# PAMonitorAP2.net
KiCad netlist of a schematic drawn in EAGLE
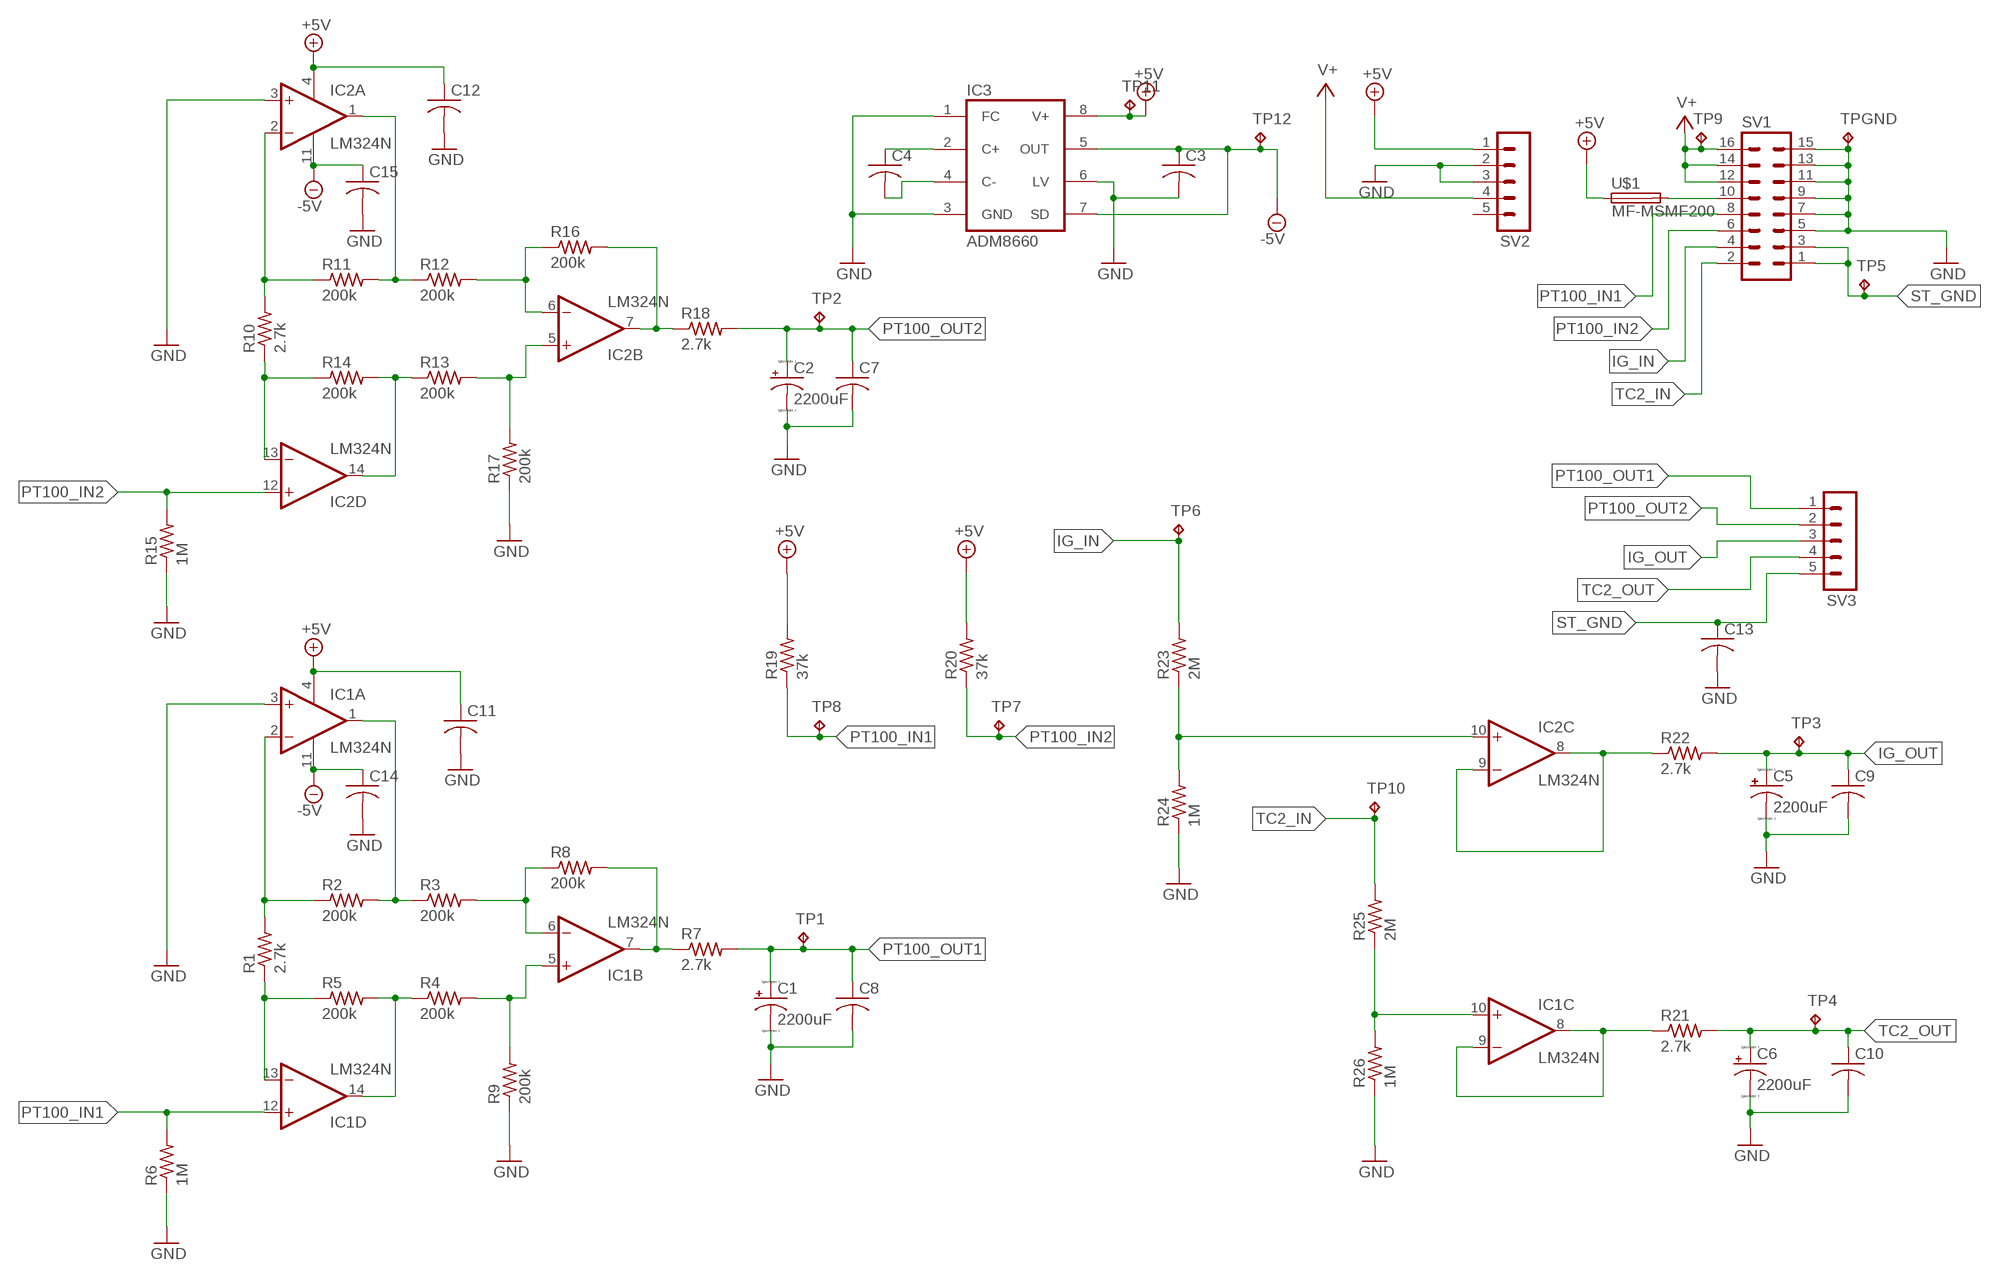
[diagram p0: schematic, sheet 1]

(export (version "E")
  (design (tool "Eeschema 10.0.6"))
  (components
    (comp (ref "C1")
      (value "2200uF")
      (footprint "eagle-import:E5-10,5")
      (libsource (lib "eagle-import") (part "CPOL-USE5-10.5"))
    )
    (comp (ref "C2")
      (value "2200uF")
      (footprint "eagle-import:E5-10,5")
      (libsource (lib "eagle-import") (part "CPOL-USE5-10.5"))
    )
    (comp (ref "C3")
      (value "C-US025-025X050")
      (footprint "eagle-import:C025-025X050")
      (libsource (lib "eagle-import") (part "C-US025-025X050"))
    )
    (comp (ref "C4")
      (value "C-US025-025X050")
      (footprint "eagle-import:C025-025X050")
      (libsource (lib "eagle-import") (part "C-US025-025X050"))
    )
    (comp (ref "C5")
      (value "2200uF")
      (footprint "eagle-import:E5-10,5")
      (libsource (lib "eagle-import") (part "CPOL-USE5-10.5"))
    )
    (comp (ref "C6")
      (value "2200uF")
      (footprint "eagle-import:E5-10,5")
      (libsource (lib "eagle-import") (part "CPOL-USE5-10.5"))
    )
    (comp (ref "C7")
      (value "C-US025-025X050")
      (footprint "eagle-import:C025-025X050")
      (libsource (lib "eagle-import") (part "C-US025-025X050"))
    )
    (comp (ref "C8")
      (value "C-US025-025X050")
      (footprint "eagle-import:C025-025X050")
      (libsource (lib "eagle-import") (part "C-US025-025X050"))
    )
    (comp (ref "C9")
      (value "C-US025-025X050")
      (footprint "eagle-import:C025-025X050")
      (libsource (lib "eagle-import") (part "C-US025-025X050"))
    )
    (comp (ref "C10")
      (value "C-US025-025X050")
      (footprint "eagle-import:C025-025X050")
      (libsource (lib "eagle-import") (part "C-US025-025X050"))
    )
    (comp (ref "C11")
      (value "C-US025-025X050")
      (footprint "eagle-import:C025-025X050")
      (libsource (lib "eagle-import") (part "C-US025-025X050"))
    )
    (comp (ref "C12")
      (value "C-US025-025X050")
      (footprint "eagle-import:C025-025X050")
      (libsource (lib "eagle-import") (part "C-US025-025X050"))
    )
    (comp (ref "C13")
      (value "C-US025-025X050")
      (footprint "eagle-import:C025-025X050")
      (libsource (lib "eagle-import") (part "C-US025-025X050"))
    )
    (comp (ref "C14")
      (value "C-US025-025X050")
      (footprint "eagle-import:C025-025X050")
      (libsource (lib "eagle-import") (part "C-US025-025X050"))
    )
    (comp (ref "C15")
      (value "C-US025-025X050")
      (footprint "eagle-import:C025-025X050")
      (libsource (lib "eagle-import") (part "C-US025-025X050"))
    )
    (comp (ref "IC1")
      (value "LM324N")
      (footprint "eagle-import:DIL14")
      (libsource (lib "eagle-import") (part "LM324N"))
    )
    (comp (ref "IC2")
      (value "LM324N")
      (footprint "eagle-import:DIL14")
      (libsource (lib "eagle-import") (part "LM324N"))
    )
    (comp (ref "IC3")
      (value "ADM8660")
      (footprint "eagle-import:ADM8660-DIL08")
      (fields (field (name "MF") "Analog Devices"))
      (libsource (lib "eagle-import") (part "ADM8660"))
    )
    (comp (ref "R1")
      (value "2.7k")
      (footprint "eagle-import:0309_12")
      (libsource (lib "eagle-import") (part "R-US_0309/12"))
    )
    (comp (ref "R2")
      (value "200k")
      (footprint "eagle-import:0309_12")
      (libsource (lib "eagle-import") (part "R-US_0309/12"))
    )
    (comp (ref "R3")
      (value "200k")
      (footprint "eagle-import:0309_12")
      (libsource (lib "eagle-import") (part "R-US_0309/12"))
    )
    (comp (ref "R4")
      (value "200k")
      (footprint "eagle-import:0309_12")
      (libsource (lib "eagle-import") (part "R-US_0309/12"))
    )
    (comp (ref "R5")
      (value "200k")
      (footprint "eagle-import:0309_12")
      (libsource (lib "eagle-import") (part "R-US_0309/12"))
    )
    (comp (ref "R6")
      (value "1M")
      (footprint "eagle-import:0309_12")
      (libsource (lib "eagle-import") (part "R-US_0309/12"))
    )
    (comp (ref "R7")
      (value "2.7k")
      (footprint "eagle-import:0309_12")
      (libsource (lib "eagle-import") (part "R-US_0309/12"))
    )
    (comp (ref "R8")
      (value "200k")
      (footprint "eagle-import:0309_12")
      (libsource (lib "eagle-import") (part "R-US_0309/12"))
    )
    (comp (ref "R9")
      (value "200k")
      (footprint "eagle-import:0309_12")
      (libsource (lib "eagle-import") (part "R-US_0309/12"))
    )
    (comp (ref "R10")
      (value "2.7k")
      (footprint "eagle-import:0309_12")
      (libsource (lib "eagle-import") (part "R-US_0309/12"))
    )
    (comp (ref "R11")
      (value "200k")
      (footprint "eagle-import:0309_12")
      (libsource (lib "eagle-import") (part "R-US_0309/12"))
    )
    (comp (ref "R12")
      (value "200k")
      (footprint "eagle-import:0309_12")
      (libsource (lib "eagle-import") (part "R-US_0309/12"))
    )
    (comp (ref "R13")
      (value "200k")
      (footprint "eagle-import:0309_12")
      (libsource (lib "eagle-import") (part "R-US_0309/12"))
    )
    (comp (ref "R14")
      (value "200k")
      (footprint "eagle-import:0309_12")
      (libsource (lib "eagle-import") (part "R-US_0309/12"))
    )
    (comp (ref "R15")
      (value "1M")
      (footprint "eagle-import:0309_12")
      (libsource (lib "eagle-import") (part "R-US_0309/12"))
    )
    (comp (ref "R16")
      (value "200k")
      (footprint "eagle-import:0309_12")
      (libsource (lib "eagle-import") (part "R-US_0309/12"))
    )
    (comp (ref "R17")
      (value "200k")
      (footprint "eagle-import:0309_12")
      (libsource (lib "eagle-import") (part "R-US_0309/12"))
    )
    (comp (ref "R18")
      (value "2.7k")
      (footprint "eagle-import:0309_12")
      (libsource (lib "eagle-import") (part "R-US_0309/12"))
    )
    (comp (ref "R19")
      (value "37k")
      (footprint "eagle-import:0309_12")
      (libsource (lib "eagle-import") (part "R-US_0309/12"))
    )
    (comp (ref "R20")
      (value "37k")
      (footprint "eagle-import:0309_12")
      (libsource (lib "eagle-import") (part "R-US_0309/12"))
    )
    (comp (ref "R21")
      (value "2.7k")
      (footprint "eagle-import:0309_12")
      (libsource (lib "eagle-import") (part "R-US_0309/12"))
    )
    (comp (ref "R22")
      (value "2.7k")
      (footprint "eagle-import:0309_12")
      (libsource (lib "eagle-import") (part "R-US_0309/12"))
    )
    (comp (ref "R23")
      (value "2M")
      (footprint "eagle-import:0309_12")
      (libsource (lib "eagle-import") (part "R-US_0309/12"))
    )
    (comp (ref "R24")
      (value "1M")
      (footprint "eagle-import:0309_12")
      (libsource (lib "eagle-import") (part "R-US_0309/12"))
    )
    (comp (ref "R25")
      (value "2M")
      (footprint "eagle-import:0309_12")
      (libsource (lib "eagle-import") (part "R-US_0309/12"))
    )
    (comp (ref "R26")
      (value "1M")
      (footprint "eagle-import:0309_12")
      (libsource (lib "eagle-import") (part "R-US_0309/12"))
    )
    (comp (ref "SV1")
      (value "MA08-2")
      (footprint "eagle-import:MA08-2")
      (libsource (lib "eagle-import") (part "MA08-2"))
    )
    (comp (ref "SV2")
      (value "MA05-1")
      (footprint "eagle-import:MA05-1")
      (libsource (lib "eagle-import") (part "MA05-1"))
    )
    (comp (ref "SV3")
      (value "MA05-1")
      (footprint "eagle-import:MA05-1")
      (libsource (lib "eagle-import") (part "MA05-1"))
    )
    (comp (ref "TP1")
      (value "TPB2,54")
      (footprint "eagle-import:B2,54")
      (libsource (lib "eagle-import") (part "TPB2,54"))
    )
    (comp (ref "TP2")
      (value "TPB2,54")
      (footprint "eagle-import:B2,54")
      (libsource (lib "eagle-import") (part "TPB2,54"))
    )
    (comp (ref "TP3")
      (value "TPB2,54")
      (footprint "eagle-import:B2,54")
      (libsource (lib "eagle-import") (part "TPB2,54"))
    )
    (comp (ref "TP4")
      (value "TPB2,54")
      (footprint "eagle-import:B2,54")
      (libsource (lib "eagle-import") (part "TPB2,54"))
    )
    (comp (ref "TP5")
      (value "TPB2,54")
      (footprint "eagle-import:B2,54")
      (libsource (lib "eagle-import") (part "TPB2,54"))
    )
    (comp (ref "TP6")
      (value "TPB2,54")
      (footprint "eagle-import:B2,54")
      (libsource (lib "eagle-import") (part "TPB2,54"))
    )
    (comp (ref "TP7")
      (value "TPB2,54")
      (footprint "eagle-import:B2,54")
      (libsource (lib "eagle-import") (part "TPB2,54"))
    )
    (comp (ref "TP8")
      (value "TPB2,54")
      (footprint "eagle-import:B2,54")
      (libsource (lib "eagle-import") (part "TPB2,54"))
    )
    (comp (ref "TP9")
      (value "TPB2,54")
      (footprint "eagle-import:B2,54")
      (libsource (lib "eagle-import") (part "TPB2,54"))
    )
    (comp (ref "TP10")
      (value "TPB2,54")
      (footprint "eagle-import:B2,54")
      (libsource (lib "eagle-import") (part "TPB2,54"))
    )
    (comp (ref "TP11")
      (value "TPB2,54")
      (footprint "eagle-import:B2,54")
      (libsource (lib "eagle-import") (part "TPB2,54"))
    )
    (comp (ref "TP12")
      (value "TPB2,54")
      (footprint "eagle-import:B2,54")
      (libsource (lib "eagle-import") (part "TPB2,54"))
    )
    (comp (ref "TPGND")
      (value "TPB2,54")
      (footprint "eagle-import:B2,54")
      (libsource (lib "eagle-import") (part "TPB2,54"))
    )
    (comp (ref "U$1")
      (value "MF-MSMF200")
      (footprint "eagle-import:MF-MSMF200")
      (libsource (lib "eagle-import") (part "MF-MSMF050"))
    )
  )
  (nets
    (net (code "1") (name "+5V") (class "Default")
      (node (ref "C11") (pin "1") (pinfunction "1_1") (pintype "passive"))
      (node (ref "C12") (pin "1") (pinfunction "1_1") (pintype "passive"))
      (node (ref "IC1") (pin "4") (pinfunction "V+_4") (pintype "power_in"))
      (node (ref "IC2") (pin "4") (pinfunction "V+_4") (pintype "power_in"))
      (node (ref "IC3") (pin "8") (pinfunction "V+_8") (pintype "power_in"))
      (node (ref "R19") (pin "2") (pinfunction "2_2") (pintype "passive"))
      (node (ref "R20") (pin "2") (pinfunction "2_2") (pintype "passive"))
      (node (ref "SV2") (pin "1") (pinfunction "1_1") (pintype "passive"))
      (node (ref "TP11") (pin "TP") (pinfunction "TP_TP") (pintype "input"))
      (node (ref "U$1") (pin "1") (pinfunction "1_1") (pintype "passive"))
    )
    (net (code "2") (name "-5V") (class "Default")
      (node (ref "C14") (pin "1") (pinfunction "1_1") (pintype "passive"))
      (node (ref "C15") (pin "1") (pinfunction "1_1") (pintype "passive"))
      (node (ref "C3") (pin "1") (pinfunction "1_1") (pintype "passive"))
      (node (ref "IC1") (pin "11") (pinfunction "V-_11") (pintype "power_in"))
      (node (ref "IC2") (pin "11") (pinfunction "V-_11") (pintype "power_in"))
      (node (ref "IC3") (pin "5") (pinfunction "OUT_5") (pintype "power_in"))
      (node (ref "IC3") (pin "7") (pinfunction "SD_7") (pintype "output"))
      (node (ref "TP12") (pin "TP") (pinfunction "TP_TP") (pintype "input"))
    )
    (net (code "3") (name "GND") (class "Default")
      (node (ref "C1") (pin "-") (pinfunction "-_-") (pintype "passive"))
      (node (ref "C10") (pin "2") (pinfunction "2_2") (pintype "passive"))
      (node (ref "C11") (pin "2") (pinfunction "2_2") (pintype "passive"))
      (node (ref "C12") (pin "2") (pinfunction "2_2") (pintype "passive"))
      (node (ref "C13") (pin "2") (pinfunction "2_2") (pintype "passive"))
      (node (ref "C14") (pin "2") (pinfunction "2_2") (pintype "passive"))
      (node (ref "C15") (pin "2") (pinfunction "2_2") (pintype "passive"))
      (node (ref "C2") (pin "-") (pinfunction "-_-") (pintype "passive"))
      (node (ref "C3") (pin "2") (pinfunction "2_2") (pintype "passive"))
      (node (ref "C5") (pin "-") (pinfunction "-_-") (pintype "passive"))
      (node (ref "C6") (pin "-") (pinfunction "-_-") (pintype "passive"))
      (node (ref "C7") (pin "2") (pinfunction "2_2") (pintype "passive"))
      (node (ref "C8") (pin "2") (pinfunction "2_2") (pintype "passive"))
      (node (ref "C9") (pin "2") (pinfunction "2_2") (pintype "passive"))
      (node (ref "IC1") (pin "3") (pinfunction "+IN_3") (pintype "input"))
      (node (ref "IC2") (pin "3") (pinfunction "+IN_3") (pintype "input"))
      (node (ref "IC3") (pin "1") (pinfunction "FC_1") (pintype "input"))
      (node (ref "IC3") (pin "3") (pinfunction "GND_3") (pintype "power_in"))
      (node (ref "IC3") (pin "6") (pinfunction "LV_6") (pintype "passive"))
      (node (ref "R15") (pin "1") (pinfunction "1_1") (pintype "passive"))
      (node (ref "R17") (pin "1") (pinfunction "1_1") (pintype "passive"))
      (node (ref "R24") (pin "1") (pinfunction "1_1") (pintype "passive"))
      (node (ref "R26") (pin "1") (pinfunction "1_1") (pintype "passive"))
      (node (ref "R6") (pin "1") (pinfunction "1_1") (pintype "passive"))
      (node (ref "R9") (pin "1") (pinfunction "1_1") (pintype "passive"))
      (node (ref "SV1") (pin "11") (pinfunction "11_11") (pintype "passive"))
      (node (ref "SV1") (pin "13") (pinfunction "13_13") (pintype "passive"))
      (node (ref "SV1") (pin "15") (pinfunction "15_15") (pintype "passive"))
      (node (ref "SV1") (pin "5") (pinfunction "5_5") (pintype "passive"))
      (node (ref "SV1") (pin "7") (pinfunction "7_7") (pintype "passive"))
      (node (ref "SV1") (pin "9") (pinfunction "9_9") (pintype "passive"))
      (node (ref "SV2") (pin "2") (pinfunction "2_2") (pintype "passive"))
      (node (ref "SV2") (pin "3") (pinfunction "3_3") (pintype "passive"))
      (node (ref "TPGND") (pin "TP") (pinfunction "TP_TP") (pintype "input"))
    )
    (net (code "4") (name "IG_IN") (class "Default")
      (node (ref "R23") (pin "2") (pinfunction "2_2") (pintype "passive"))
      (node (ref "SV1") (pin "4") (pinfunction "4_4") (pintype "passive"))
      (node (ref "TP6") (pin "TP") (pinfunction "TP_TP") (pintype "input"))
    )
    (net (code "5") (name "IG_OUT") (class "Default")
      (node (ref "C5") (pin "+") (pinfunction "+_+") (pintype "passive"))
      (node (ref "C9") (pin "1") (pinfunction "1_1") (pintype "passive"))
      (node (ref "R22") (pin "2") (pinfunction "2_2") (pintype "passive"))
      (node (ref "SV3") (pin "3") (pinfunction "3_3") (pintype "passive"))
      (node (ref "TP3") (pin "TP") (pinfunction "TP_TP") (pintype "input"))
    )
    (net (code "6") (name "Net-(IC1A--IN)") (class "Default")
      (node (ref "IC1") (pin "2") (pinfunction "-IN_2") (pintype "input"))
      (node (ref "R1") (pin "2") (pinfunction "2_2") (pintype "passive"))
      (node (ref "R2") (pin "1") (pinfunction "1_1") (pintype "passive"))
    )
    (net (code "7") (name "Net-(IC1A-OUT)") (class "Default")
      (node (ref "IC1") (pin "1") (pinfunction "OUT_1") (pintype "output"))
      (node (ref "R2") (pin "2") (pinfunction "2_2") (pintype "passive"))
      (node (ref "R3") (pin "1") (pinfunction "1_1") (pintype "passive"))
    )
    (net (code "8") (name "Net-(IC1B-+IN)") (class "Default")
      (node (ref "IC1") (pin "5") (pinfunction "+IN_5") (pintype "input"))
      (node (ref "R4") (pin "2") (pinfunction "2_2") (pintype "passive"))
      (node (ref "R9") (pin "2") (pinfunction "2_2") (pintype "passive"))
    )
    (net (code "9") (name "Net-(IC1B--IN)") (class "Default")
      (node (ref "IC1") (pin "6") (pinfunction "-IN_6") (pintype "input"))
      (node (ref "R3") (pin "2") (pinfunction "2_2") (pintype "passive"))
      (node (ref "R8") (pin "1") (pinfunction "1_1") (pintype "passive"))
    )
    (net (code "10") (name "Net-(IC1B-OUT)") (class "Default")
      (node (ref "IC1") (pin "7") (pinfunction "OUT_7") (pintype "output"))
      (node (ref "R7") (pin "1") (pinfunction "1_1") (pintype "passive"))
      (node (ref "R8") (pin "2") (pinfunction "2_2") (pintype "passive"))
    )
    (net (code "11") (name "Net-(IC1C-+IN)") (class "Default")
      (node (ref "IC1") (pin "10") (pinfunction "+IN_10") (pintype "input"))
      (node (ref "R25") (pin "1") (pinfunction "1_1") (pintype "passive"))
      (node (ref "R26") (pin "2") (pinfunction "2_2") (pintype "passive"))
    )
    (net (code "12") (name "Net-(IC1C--IN)") (class "Default")
      (node (ref "IC1") (pin "8") (pinfunction "OUT_8") (pintype "output"))
      (node (ref "IC1") (pin "9") (pinfunction "-IN_9") (pintype "input"))
      (node (ref "R21") (pin "1") (pinfunction "1_1") (pintype "passive"))
    )
    (net (code "13") (name "Net-(IC1D--IN)") (class "Default")
      (node (ref "IC1") (pin "13") (pinfunction "-IN_13") (pintype "input"))
      (node (ref "R1") (pin "1") (pinfunction "1_1") (pintype "passive"))
      (node (ref "R5") (pin "1") (pinfunction "1_1") (pintype "passive"))
    )
    (net (code "14") (name "Net-(IC1D-OUT)") (class "Default")
      (node (ref "IC1") (pin "14") (pinfunction "OUT_14") (pintype "output"))
      (node (ref "R4") (pin "1") (pinfunction "1_1") (pintype "passive"))
      (node (ref "R5") (pin "2") (pinfunction "2_2") (pintype "passive"))
    )
    (net (code "15") (name "Net-(IC2A--IN)") (class "Default")
      (node (ref "IC2") (pin "2") (pinfunction "-IN_2") (pintype "input"))
      (node (ref "R10") (pin "2") (pinfunction "2_2") (pintype "passive"))
      (node (ref "R11") (pin "1") (pinfunction "1_1") (pintype "passive"))
    )
    (net (code "16") (name "Net-(IC2A-OUT)") (class "Default")
      (node (ref "IC2") (pin "1") (pinfunction "OUT_1") (pintype "output"))
      (node (ref "R11") (pin "2") (pinfunction "2_2") (pintype "passive"))
      (node (ref "R12") (pin "1") (pinfunction "1_1") (pintype "passive"))
    )
    (net (code "17") (name "Net-(IC2B-+IN)") (class "Default")
      (node (ref "IC2") (pin "5") (pinfunction "+IN_5") (pintype "input"))
      (node (ref "R13") (pin "2") (pinfunction "2_2") (pintype "passive"))
      (node (ref "R17") (pin "2") (pinfunction "2_2") (pintype "passive"))
    )
    (net (code "18") (name "Net-(IC2B--IN)") (class "Default")
      (node (ref "IC2") (pin "6") (pinfunction "-IN_6") (pintype "input"))
      (node (ref "R12") (pin "2") (pinfunction "2_2") (pintype "passive"))
      (node (ref "R16") (pin "1") (pinfunction "1_1") (pintype "passive"))
    )
    (net (code "19") (name "Net-(IC2B-OUT)") (class "Default")
      (node (ref "IC2") (pin "7") (pinfunction "OUT_7") (pintype "output"))
      (node (ref "R16") (pin "2") (pinfunction "2_2") (pintype "passive"))
      (node (ref "R18") (pin "1") (pinfunction "1_1") (pintype "passive"))
    )
    (net (code "20") (name "Net-(IC2C-+IN)") (class "Default")
      (node (ref "IC2") (pin "10") (pinfunction "+IN_10") (pintype "input"))
      (node (ref "R23") (pin "1") (pinfunction "1_1") (pintype "passive"))
      (node (ref "R24") (pin "2") (pinfunction "2_2") (pintype "passive"))
    )
    (net (code "21") (name "Net-(IC2C--IN)") (class "Default")
      (node (ref "IC2") (pin "8") (pinfunction "OUT_8") (pintype "output"))
      (node (ref "IC2") (pin "9") (pinfunction "-IN_9") (pintype "input"))
      (node (ref "R22") (pin "1") (pinfunction "1_1") (pintype "passive"))
    )
    (net (code "22") (name "Net-(IC2D--IN)") (class "Default")
      (node (ref "IC2") (pin "13") (pinfunction "-IN_13") (pintype "input"))
      (node (ref "R10") (pin "1") (pinfunction "1_1") (pintype "passive"))
      (node (ref "R14") (pin "1") (pinfunction "1_1") (pintype "passive"))
    )
    (net (code "23") (name "Net-(IC2D-OUT)") (class "Default")
      (node (ref "IC2") (pin "14") (pinfunction "OUT_14") (pintype "output"))
      (node (ref "R13") (pin "1") (pinfunction "1_1") (pintype "passive"))
      (node (ref "R14") (pin "2") (pinfunction "2_2") (pintype "passive"))
    )
    (net (code "24") (name "Net-(IC3-C+)") (class "Default")
      (node (ref "C4") (pin "1") (pinfunction "1_1") (pintype "passive"))
      (node (ref "IC3") (pin "2") (pinfunction "C+_2") (pintype "passive"))
    )
    (net (code "25") (name "Net-(IC3-C-)") (class "Default")
      (node (ref "C4") (pin "2") (pinfunction "2_2") (pintype "passive"))
      (node (ref "IC3") (pin "4") (pinfunction "C-_4") (pintype "passive"))
    )
    (net (code "26") (name "Net-(SV1-Pad10)") (class "Default")
      (node (ref "SV1") (pin "10") (pinfunction "10_10") (pintype "passive"))
      (node (ref "U$1") (pin "2") (pinfunction "2_2") (pintype "passive"))
    )
    (net (code "27") (name "PT100_IN1") (class "Default")
      (node (ref "IC1") (pin "12") (pinfunction "+IN_12") (pintype "input"))
      (node (ref "R19") (pin "1") (pinfunction "1_1") (pintype "passive"))
      (node (ref "R6") (pin "2") (pinfunction "2_2") (pintype "passive"))
      (node (ref "SV1") (pin "8") (pinfunction "8_8") (pintype "passive"))
      (node (ref "TP8") (pin "TP") (pinfunction "TP_TP") (pintype "input"))
    )
    (net (code "28") (name "PT100_IN2") (class "Default")
      (node (ref "IC2") (pin "12") (pinfunction "+IN_12") (pintype "input"))
      (node (ref "R15") (pin "2") (pinfunction "2_2") (pintype "passive"))
      (node (ref "R20") (pin "1") (pinfunction "1_1") (pintype "passive"))
      (node (ref "SV1") (pin "6") (pinfunction "6_6") (pintype "passive"))
      (node (ref "TP7") (pin "TP") (pinfunction "TP_TP") (pintype "input"))
    )
    (net (code "29") (name "PT100_OUT1") (class "Default")
      (node (ref "C1") (pin "+") (pinfunction "+_+") (pintype "passive"))
      (node (ref "C8") (pin "1") (pinfunction "1_1") (pintype "passive"))
      (node (ref "R7") (pin "2") (pinfunction "2_2") (pintype "passive"))
      (node (ref "SV3") (pin "1") (pinfunction "1_1") (pintype "passive"))
      (node (ref "TP1") (pin "TP") (pinfunction "TP_TP") (pintype "input"))
    )
    (net (code "30") (name "PT100_OUT2") (class "Default")
      (node (ref "C2") (pin "+") (pinfunction "+_+") (pintype "passive"))
      (node (ref "C7") (pin "1") (pinfunction "1_1") (pintype "passive"))
      (node (ref "R18") (pin "2") (pinfunction "2_2") (pintype "passive"))
      (node (ref "SV3") (pin "2") (pinfunction "2_2") (pintype "passive"))
      (node (ref "TP2") (pin "TP") (pinfunction "TP_TP") (pintype "input"))
    )
    (net (code "31") (name "ST_GND") (class "Default")
      (node (ref "C13") (pin "1") (pinfunction "1_1") (pintype "passive"))
      (node (ref "SV1") (pin "1") (pinfunction "1_1") (pintype "passive"))
      (node (ref "SV1") (pin "3") (pinfunction "3_3") (pintype "passive"))
      (node (ref "SV3") (pin "5") (pinfunction "5_5") (pintype "passive"))
      (node (ref "TP5") (pin "TP") (pinfunction "TP_TP") (pintype "input"))
    )
    (net (code "32") (name "TC2_IN") (class "Default")
      (node (ref "R25") (pin "2") (pinfunction "2_2") (pintype "passive"))
      (node (ref "SV1") (pin "2") (pinfunction "2_2") (pintype "passive"))
      (node (ref "TP10") (pin "TP") (pinfunction "TP_TP") (pintype "input"))
    )
    (net (code "33") (name "TC2_OUT") (class "Default")
      (node (ref "C10") (pin "1") (pinfunction "1_1") (pintype "passive"))
      (node (ref "C6") (pin "+") (pinfunction "+_+") (pintype "passive"))
      (node (ref "R21") (pin "2") (pinfunction "2_2") (pintype "passive"))
      (node (ref "SV3") (pin "4") (pinfunction "4_4") (pintype "passive"))
      (node (ref "TP4") (pin "TP") (pinfunction "TP_TP") (pintype "input"))
    )
    (net (code "34") (name "V+") (class "Default")
      (node (ref "SV1") (pin "12") (pinfunction "12_12") (pintype "passive"))
      (node (ref "SV1") (pin "14") (pinfunction "14_14") (pintype "passive"))
      (node (ref "SV1") (pin "16") (pinfunction "16_16") (pintype "passive"))
      (node (ref "SV2") (pin "4") (pinfunction "4_4") (pintype "passive"))
      (node (ref "TP9") (pin "TP") (pinfunction "TP_TP") (pintype "input"))
    )
    (net (code "35") (name "unconnected-(SV2-Pad5)") (class "Default")
      (node (ref "SV2") (pin "5") (pinfunction "5_5") (pintype "passive"))
    )
  )
)
